# INPUT_1.net
KiCad netlist of a schematic drawn in EAGLE
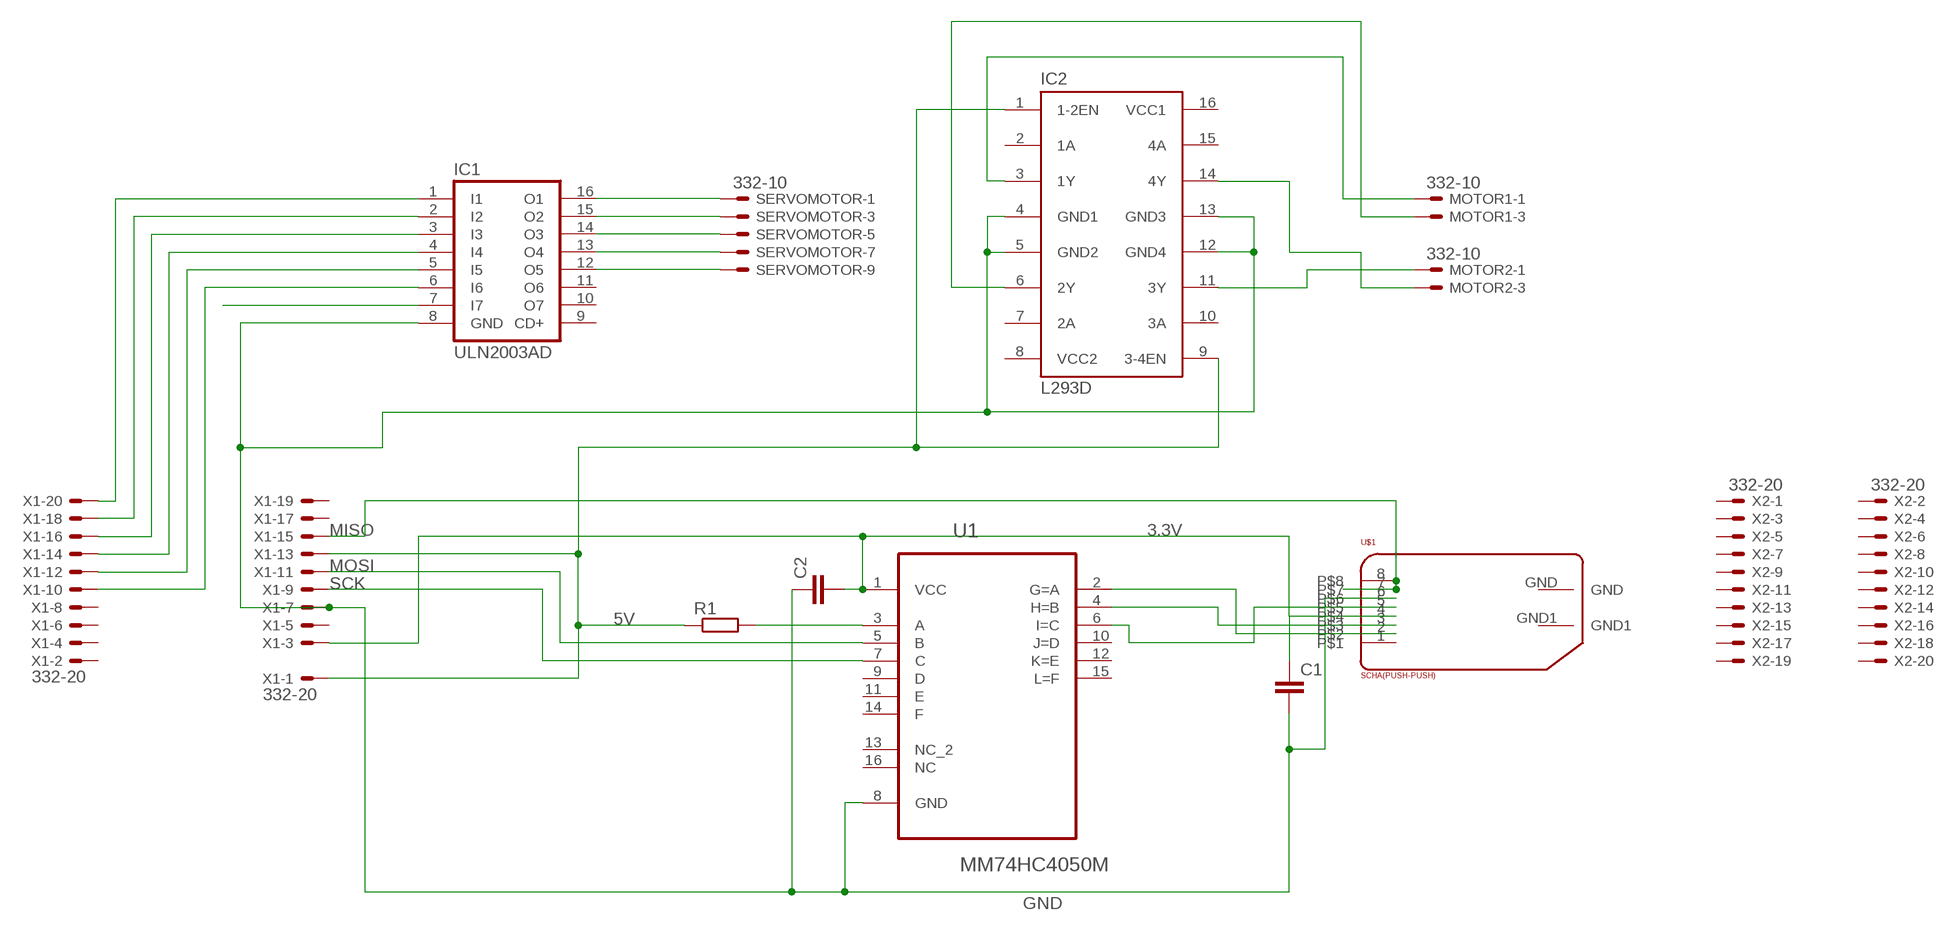
[diagram p0: schematic, sheet 1]

(export (version "E")
  (design (tool "Eeschema 10.0.6"))
  (components
    (comp (ref "C1")
      (value "C-EUC0603")
      (footprint "eagle-import:C0603")
      (libsource (lib "eagle-import") (part "C-EUC0603"))
    )
    (comp (ref "C2")
      (value "C-EUC0603")
      (footprint "eagle-import:C0603")
      (libsource (lib "eagle-import") (part "C-EUC0603"))
    )
    (comp (ref "IC1")
      (value "ULN2003AD")
      (footprint "eagle-import:SO16")
      (libsource (lib "eagle-import") (part "ULN2003AD"))
    )
    (comp (ref "IC2")
      (value "L293D")
      (footprint "eagle-import:DIL16")
      (libsource (lib "eagle-import") (part "L293D"))
    )
    (comp (ref "MOTOR1")
      (value "332-10")
      (footprint "eagle-import:332-10")
      (libsource (lib "eagle-import") (part "332-10"))
    )
    (comp (ref "MOTOR2")
      (value "332-10")
      (footprint "eagle-import:332-10")
      (libsource (lib "eagle-import") (part "332-10"))
    )
    (comp (ref "R1")
      (value "R-EU_R0603")
      (footprint "eagle-import:R0603")
      (libsource (lib "eagle-import") (part "R-EU_R0603"))
    )
    (comp (ref "SERVOMOTOR")
      (value "332-10")
      (footprint "eagle-import:332-10")
      (libsource (lib "eagle-import") (part "332-10"))
    )
    (comp (ref "U$1")
      (value "SCHA(PUSH-PUSH)")
      (footprint "eagle-import:SCHA(PUCH-PUCH_TYPE)")
      (libsource (lib "eagle-import") (part "SCHA(PUSH-PUSH)"))
    )
    (comp (ref "U1")
      (value "MM74HC4050M")
      (footprint "eagle-import:SOIC127P600X175-16N")
      (fields (field (name "MF") "ON Semiconductor"))
      (libsource (lib "eagle-import") (part "MM74HC4050M"))
    )
    (comp (ref "X1")
      (value "332-20")
      (footprint "eagle-import:332-20")
      (libsource (lib "eagle-import") (part "332-20"))
    )
    (comp (ref "X2")
      (value "332-20")
      (footprint "eagle-import:332-20")
      (libsource (lib "eagle-import") (part "332-20"))
    )
  )
  (nets
    (net (code "1") (name "/3.3V") (class "Default")
      (node (ref "C1") (pin "1") (pinfunction "1_1") (pintype "passive"))
      (node (ref "C2") (pin "2") (pinfunction "2_2") (pintype "passive"))
      (node (ref "U$1") (pin "4") (pinfunction "P$4_4") (pintype "bidirectional"))
      (node (ref "U1") (pin "1") (pinfunction "VCC_1") (pintype "power_in"))
      (node (ref "X1") (pin "3") (pinfunction "S_3") (pintype "passive"))
    )
    (net (code "2") (name "/5V") (class "Default")
      (node (ref "IC2") (pin "1") (pinfunction "1-2EN_1") (pintype "input"))
      (node (ref "IC2") (pin "9") (pinfunction "3-4EN_9") (pintype "input"))
      (node (ref "R1") (pin "1") (pinfunction "1_1") (pintype "passive"))
      (node (ref "X1") (pin "1") (pinfunction "S_1") (pintype "passive"))
      (node (ref "X1") (pin "13") (pinfunction "S_13") (pintype "passive"))
    )
    (net (code "3") (name "/GND") (class "Default")
      (node (ref "C1") (pin "2") (pinfunction "2_2") (pintype "passive"))
      (node (ref "C2") (pin "1") (pinfunction "1_1") (pintype "passive"))
      (node (ref "IC1") (pin "8") (pinfunction "GND_8") (pintype "power_in"))
      (node (ref "IC2") (pin "12") (pinfunction "GND4_12") (pintype "power_in"))
      (node (ref "IC2") (pin "13") (pinfunction "GND3_13") (pintype "power_in"))
      (node (ref "IC2") (pin "4") (pinfunction "GND1_4") (pintype "power_in"))
      (node (ref "IC2") (pin "5") (pinfunction "GND2_5") (pintype "power_in"))
      (node (ref "U$1") (pin "6") (pinfunction "P$6_6") (pintype "bidirectional"))
      (node (ref "U1") (pin "8") (pinfunction "GND_8") (pintype "passive"))
      (node (ref "X1") (pin "7") (pinfunction "S_7") (pintype "passive"))
    )
    (net (code "4") (name "/MISO") (class "Default")
      (node (ref "U$1") (pin "7") (pinfunction "P$7_7") (pintype "bidirectional"))
      (node (ref "U$1") (pin "8") (pinfunction "P$8_8") (pintype "bidirectional"))
      (node (ref "X1") (pin "15") (pinfunction "S_15") (pintype "passive"))
    )
    (net (code "5") (name "/MOSI") (class "Default")
      (node (ref "U1") (pin "5") (pinfunction "B_5") (pintype "input"))
      (node (ref "X1") (pin "11") (pinfunction "S_11") (pintype "passive"))
    )
    (net (code "6") (name "/SCK") (class "Default")
      (node (ref "U1") (pin "7") (pinfunction "C_7") (pintype "input"))
      (node (ref "X1") (pin "9") (pinfunction "S_9") (pintype "passive"))
    )
    (net (code "7") (name "/VCC1") (class "Default")
      (node (ref "IC2") (pin "16") (pinfunction "VCC1_16") (pintype "power_in"))
    )
    (net (code "8") (name "/VCC2") (class "Default")
      (node (ref "IC2") (pin "8") (pinfunction "VCC2_8") (pintype "power_in"))
    )
    (net (code "9") (name "Net-(IC1-I1)") (class "Default")
      (node (ref "IC1") (pin "1") (pinfunction "I1_1") (pintype "input"))
      (node (ref "X1") (pin "20") (pinfunction "S_20") (pintype "passive"))
    )
    (net (code "10") (name "Net-(IC1-I2)") (class "Default")
      (node (ref "IC1") (pin "2") (pinfunction "I2_2") (pintype "input"))
      (node (ref "X1") (pin "18") (pinfunction "S_18") (pintype "passive"))
    )
    (net (code "11") (name "Net-(IC1-I3)") (class "Default")
      (node (ref "IC1") (pin "3") (pinfunction "I3_3") (pintype "input"))
      (node (ref "X1") (pin "16") (pinfunction "S_16") (pintype "passive"))
    )
    (net (code "12") (name "Net-(IC1-I4)") (class "Default")
      (node (ref "IC1") (pin "4") (pinfunction "I4_4") (pintype "input"))
      (node (ref "X1") (pin "14") (pinfunction "S_14") (pintype "passive"))
    )
    (net (code "13") (name "Net-(IC1-I5)") (class "Default")
      (node (ref "IC1") (pin "5") (pinfunction "I5_5") (pintype "input"))
      (node (ref "X1") (pin "12") (pinfunction "S_12") (pintype "passive"))
    )
    (net (code "14") (name "Net-(IC1-I6)") (class "Default")
      (node (ref "IC1") (pin "6") (pinfunction "I6_6") (pintype "input"))
      (node (ref "X1") (pin "10") (pinfunction "S_10") (pintype "passive"))
    )
    (net (code "15") (name "Net-(IC1-O1)") (class "Default")
      (node (ref "IC1") (pin "16") (pinfunction "O1_16") (pintype "open_collector"))
      (node (ref "SERVOMOTOR") (pin "1") (pinfunction "S_1") (pintype "passive"))
    )
    (net (code "16") (name "Net-(IC1-O2)") (class "Default")
      (node (ref "IC1") (pin "15") (pinfunction "O2_15") (pintype "open_collector"))
      (node (ref "SERVOMOTOR") (pin "3") (pinfunction "S_3") (pintype "passive"))
    )
    (net (code "17") (name "Net-(IC1-O3)") (class "Default")
      (node (ref "IC1") (pin "14") (pinfunction "O3_14") (pintype "open_collector"))
      (node (ref "SERVOMOTOR") (pin "5") (pinfunction "S_5") (pintype "passive"))
    )
    (net (code "18") (name "Net-(IC1-O4)") (class "Default")
      (node (ref "IC1") (pin "13") (pinfunction "O4_13") (pintype "open_collector"))
      (node (ref "SERVOMOTOR") (pin "7") (pinfunction "S_7") (pintype "passive"))
    )
    (net (code "19") (name "Net-(IC1-O5)") (class "Default")
      (node (ref "IC1") (pin "12") (pinfunction "O5_12") (pintype "open_collector"))
      (node (ref "SERVOMOTOR") (pin "9") (pinfunction "S_9") (pintype "passive"))
    )
    (net (code "20") (name "Net-(IC2-1Y)") (class "Default")
      (node (ref "IC2") (pin "3") (pinfunction "1Y_3") (pintype "output"))
      (node (ref "MOTOR1") (pin "1") (pinfunction "S_1") (pintype "passive"))
    )
    (net (code "21") (name "Net-(IC2-2Y)") (class "Default")
      (node (ref "IC2") (pin "6") (pinfunction "2Y_6") (pintype "output"))
      (node (ref "MOTOR1") (pin "3") (pinfunction "S_3") (pintype "passive"))
    )
    (net (code "22") (name "Net-(IC2-3Y)") (class "Default")
      (node (ref "IC2") (pin "11") (pinfunction "3Y_11") (pintype "output"))
      (node (ref "MOTOR2") (pin "1") (pinfunction "S_1") (pintype "passive"))
    )
    (net (code "23") (name "Net-(IC2-4Y)") (class "Default")
      (node (ref "IC2") (pin "14") (pinfunction "4Y_14") (pintype "output"))
      (node (ref "MOTOR2") (pin "3") (pinfunction "S_3") (pintype "passive"))
    )
    (net (code "24") (name "Net-(U$1-P$2)") (class "Default")
      (node (ref "U$1") (pin "2") (pinfunction "P$2_2") (pintype "bidirectional"))
      (node (ref "U1") (pin "2") (pinfunction "G=A_2") (pintype "output"))
    )
    (net (code "25") (name "Net-(U$1-P$3)") (class "Default")
      (node (ref "U$1") (pin "3") (pinfunction "P$3_3") (pintype "bidirectional"))
      (node (ref "U1") (pin "4") (pinfunction "H=B_4") (pintype "output"))
    )
    (net (code "26") (name "Net-(U$1-P$5)") (class "Default")
      (node (ref "U$1") (pin "5") (pinfunction "P$5_5") (pintype "bidirectional"))
      (node (ref "U1") (pin "6") (pinfunction "I=C_6") (pintype "output"))
    )
    (net (code "27") (name "Net-(U1-A)") (class "Default")
      (node (ref "R1") (pin "2") (pinfunction "2_2") (pintype "passive"))
      (node (ref "U1") (pin "3") (pinfunction "A_3") (pintype "input"))
    )
    (net (code "28") (name "unconnected-(IC1-CD+-Pad9)") (class "Default")
      (node (ref "IC1") (pin "9") (pinfunction "CD+_9") (pintype "passive"))
    )
    (net (code "29") (name "unconnected-(IC1-I7-Pad7)") (class "Default")
      (node (ref "IC1") (pin "7") (pinfunction "I7_7") (pintype "input"))
    )
    (net (code "30") (name "unconnected-(IC1-O6-Pad11)") (class "Default")
      (node (ref "IC1") (pin "11") (pinfunction "O6_11") (pintype "open_collector"))
    )
    (net (code "31") (name "unconnected-(IC1-O7-Pad10)") (class "Default")
      (node (ref "IC1") (pin "10") (pinfunction "O7_10") (pintype "open_collector"))
    )
    (net (code "32") (name "unconnected-(IC2-1A-Pad2)") (class "Default")
      (node (ref "IC2") (pin "2") (pinfunction "1A_2") (pintype "input"))
    )
    (net (code "33") (name "unconnected-(IC2-2A-Pad7)") (class "Default")
      (node (ref "IC2") (pin "7") (pinfunction "2A_7") (pintype "input"))
    )
    (net (code "34") (name "unconnected-(IC2-3A-Pad10)") (class "Default")
      (node (ref "IC2") (pin "10") (pinfunction "3A_10") (pintype "input"))
    )
    (net (code "35") (name "unconnected-(IC2-4A-Pad15)") (class "Default")
      (node (ref "IC2") (pin "15") (pinfunction "4A_15") (pintype "input"))
    )
    (net (code "36") (name "unconnected-(U$1-P$1-Pad1)") (class "Default")
      (node (ref "U$1") (pin "1") (pinfunction "P$1_1") (pintype "bidirectional"))
    )
    (net (code "37") (name "unconnected-(U$1-PadGND)") (class "Default")
      (node (ref "U$1") (pin "GND") (pinfunction "GND_GND") (pintype "bidirectional"))
    )
    (net (code "38") (name "unconnected-(U$1-PadGND1)") (class "Default")
      (node (ref "U$1") (pin "GND1") (pinfunction "GND1_GND1") (pintype "bidirectional"))
    )
    (net (code "39") (name "unconnected-(U1-D-Pad9)") (class "Default")
      (node (ref "U1") (pin "9") (pinfunction "D_9") (pintype "input"))
    )
    (net (code "40") (name "unconnected-(U1-E-Pad11)") (class "Default")
      (node (ref "U1") (pin "11") (pinfunction "E_11") (pintype "input"))
    )
    (net (code "41") (name "unconnected-(U1-F-Pad14)") (class "Default")
      (node (ref "U1") (pin "14") (pinfunction "F_14") (pintype "input"))
    )
    (net (code "42") (name "unconnected-(U1-J=D-Pad10)") (class "Default")
      (node (ref "U1") (pin "10") (pinfunction "J=D_10") (pintype "output"))
    )
    (net (code "43") (name "unconnected-(U1-K=E-Pad12)") (class "Default")
      (node (ref "U1") (pin "12") (pinfunction "K=E_12") (pintype "output"))
    )
    (net (code "44") (name "unconnected-(U1-L=F-Pad15)") (class "Default")
      (node (ref "U1") (pin "15") (pinfunction "L=F_15") (pintype "output"))
    )
    (net (code "45") (name "unconnected-(U1-NC-Pad16)") (class "Default")
      (node (ref "U1") (pin "16") (pinfunction "NC_16") (pintype "no_connect"))
    )
    (net (code "46") (name "unconnected-(U1-NC_2-Pad13)") (class "Default")
      (node (ref "U1") (pin "13") (pinfunction "NC_2_13") (pintype "no_connect"))
    )
    (net (code "47") (name "unconnected-(X1I-S-Pad17)") (class "Default")
      (node (ref "X1") (pin "17") (pinfunction "S_17") (pintype "passive"))
    )
    (net (code "48") (name "unconnected-(X1K-S-Pad19)") (class "Default")
      (node (ref "X1") (pin "19") (pinfunction "S_19") (pintype "passive"))
    )
    (net (code "49") (name "unconnected-(X1L-S-Pad2)") (class "Default")
      (node (ref "X1") (pin "2") (pinfunction "S_2") (pintype "passive"))
    )
    (net (code "50") (name "unconnected-(X1O-S-Pad4)") (class "Default")
      (node (ref "X1") (pin "4") (pinfunction "S_4") (pintype "passive"))
    )
    (net (code "51") (name "unconnected-(X1P-S-Pad5)") (class "Default")
      (node (ref "X1") (pin "5") (pinfunction "S_5") (pintype "passive"))
    )
    (net (code "52") (name "unconnected-(X1Q-S-Pad6)") (class "Default")
      (node (ref "X1") (pin "6") (pinfunction "S_6") (pintype "passive"))
    )
    (net (code "53") (name "unconnected-(X1S-S-Pad8)") (class "Default")
      (node (ref "X1") (pin "8") (pinfunction "S_8") (pintype "passive"))
    )
    (net (code "54") (name "unconnected-(X2A-S-Pad1)") (class "Default")
      (node (ref "X2") (pin "1") (pinfunction "S_1") (pintype "passive"))
    )
    (net (code "55") (name "unconnected-(X2B-S-Pad10)") (class "Default")
      (node (ref "X2") (pin "10") (pinfunction "S_10") (pintype "passive"))
    )
    (net (code "56") (name "unconnected-(X2C-S-Pad11)") (class "Default")
      (node (ref "X2") (pin "11") (pinfunction "S_11") (pintype "passive"))
    )
    (net (code "57") (name "unconnected-(X2D-S-Pad12)") (class "Default")
      (node (ref "X2") (pin "12") (pinfunction "S_12") (pintype "passive"))
    )
    (net (code "58") (name "unconnected-(X2E-S-Pad13)") (class "Default")
      (node (ref "X2") (pin "13") (pinfunction "S_13") (pintype "passive"))
    )
    (net (code "59") (name "unconnected-(X2F-S-Pad14)") (class "Default")
      (node (ref "X2") (pin "14") (pinfunction "S_14") (pintype "passive"))
    )
    (net (code "60") (name "unconnected-(X2G-S-Pad15)") (class "Default")
      (node (ref "X2") (pin "15") (pinfunction "S_15") (pintype "passive"))
    )
    (net (code "61") (name "unconnected-(X2H-S-Pad16)") (class "Default")
      (node (ref "X2") (pin "16") (pinfunction "S_16") (pintype "passive"))
    )
    (net (code "62") (name "unconnected-(X2I-S-Pad17)") (class "Default")
      (node (ref "X2") (pin "17") (pinfunction "S_17") (pintype "passive"))
    )
    (net (code "63") (name "unconnected-(X2J-S-Pad18)") (class "Default")
      (node (ref "X2") (pin "18") (pinfunction "S_18") (pintype "passive"))
    )
    (net (code "64") (name "unconnected-(X2K-S-Pad19)") (class "Default")
      (node (ref "X2") (pin "19") (pinfunction "S_19") (pintype "passive"))
    )
    (net (code "65") (name "unconnected-(X2L-S-Pad2)") (class "Default")
      (node (ref "X2") (pin "2") (pinfunction "S_2") (pintype "passive"))
    )
    (net (code "66") (name "unconnected-(X2M-S-Pad20)") (class "Default")
      (node (ref "X2") (pin "20") (pinfunction "S_20") (pintype "passive"))
    )
    (net (code "67") (name "unconnected-(X2N-S-Pad3)") (class "Default")
      (node (ref "X2") (pin "3") (pinfunction "S_3") (pintype "passive"))
    )
    (net (code "68") (name "unconnected-(X2O-S-Pad4)") (class "Default")
      (node (ref "X2") (pin "4") (pinfunction "S_4") (pintype "passive"))
    )
    (net (code "69") (name "unconnected-(X2P-S-Pad5)") (class "Default")
      (node (ref "X2") (pin "5") (pinfunction "S_5") (pintype "passive"))
    )
    (net (code "70") (name "unconnected-(X2Q-S-Pad6)") (class "Default")
      (node (ref "X2") (pin "6") (pinfunction "S_6") (pintype "passive"))
    )
    (net (code "71") (name "unconnected-(X2R-S-Pad7)") (class "Default")
      (node (ref "X2") (pin "7") (pinfunction "S_7") (pintype "passive"))
    )
    (net (code "72") (name "unconnected-(X2S-S-Pad8)") (class "Default")
      (node (ref "X2") (pin "8") (pinfunction "S_8") (pintype "passive"))
    )
    (net (code "73") (name "unconnected-(X2T-S-Pad9)") (class "Default")
      (node (ref "X2") (pin "9") (pinfunction "S_9") (pintype "passive"))
    )
  )
)
